# MotorBoard_PowerDistribution.net
KiCad netlist of a schematic drawn in Altium Designer
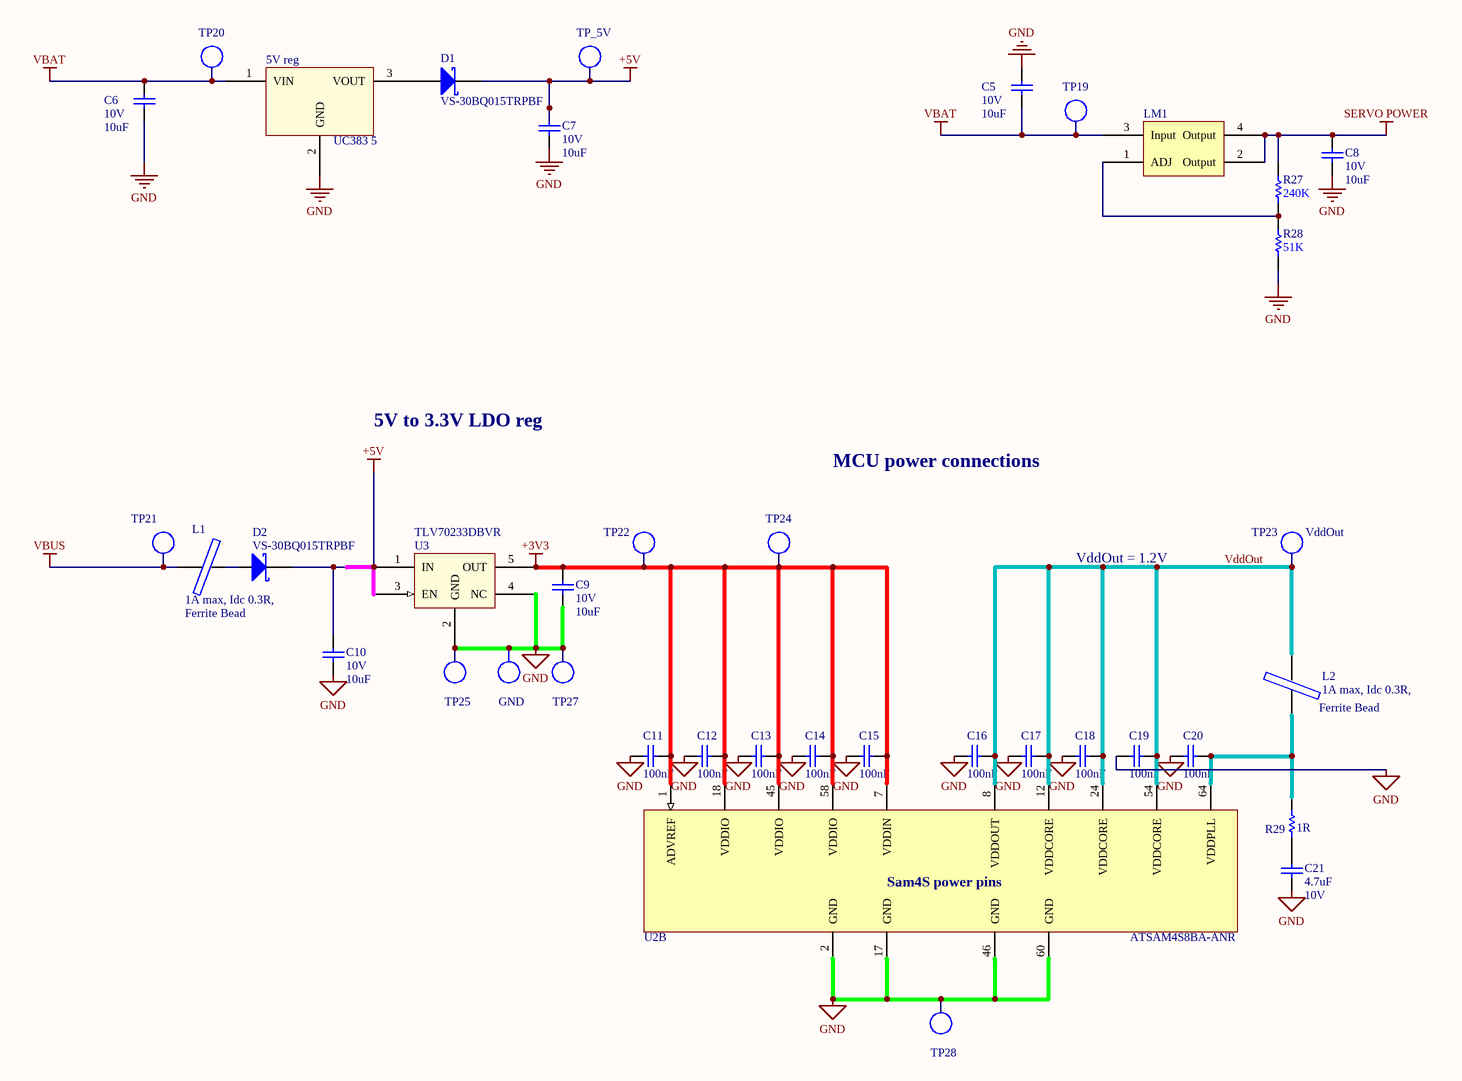
[diagram p0: MotorBoard_PowerDistribution.SchDoc]

(export (version "E")
  (design (tool "Eeschema 10.0.6"))
  (components
    (comp (ref "5V reg")
      (value "UC383 5")
      (footprint "UC383-5")
      (libsource (lib "UC383_5_Throughole_Regulator") (part "UC383 5"))
    )
    (comp (ref "C5")
      (value "10uF")
      (footprint "CAPC1608L")
      (description "CAP CER 10UF X5R +-20% 10V 0603")
      (fields (field (name "VOLTAGE - RATED") "10V"))
      (libsource (lib "ECE Components_15_7") (part "CC_10uF_0603"))
    )
    (comp (ref "C6")
      (value "10uF")
      (footprint "CAPC1608L")
      (description "CAP CER 10UF X5R +-20% 10V 0603")
      (fields (field (name "VOLTAGE - RATED") "10V"))
      (libsource (lib "ECE Components_15_7") (part "CC_10uF_0603"))
    )
    (comp (ref "C7")
      (value "10uF")
      (footprint "CAPC1608L")
      (description "CAP CER 10UF X5R +-20% 10V 0603")
      (fields (field (name "VOLTAGE - RATED") "10V"))
      (libsource (lib "ECE Components_15_7") (part "CC_10uF_0603"))
    )
    (comp (ref "C8")
      (value "10uF")
      (footprint "CAPC1608L")
      (description "CAP CER 10UF X5R +-20% 10V 0603")
      (fields (field (name "VOLTAGE - RATED") "10V"))
      (libsource (lib "ECE Components_15_7") (part "CC_10uF_0603"))
    )
    (comp (ref "C9")
      (value "10uF")
      (footprint "CAPC1608L")
      (description "CAP CER 10UF X5R +-20% 10V 0603")
      (fields (field (name "VOLTAGE - RATED") "10V"))
      (libsource (lib "ECE Components_15_7") (part "CC_10uF_0603"))
    )
    (comp (ref "C10")
      (value "10uF")
      (footprint "CAPC1608L")
      (description "CAP CER 10UF X5R +-20% 10V 0603")
      (fields (field (name "VOLTAGE - RATED") "10V"))
      (libsource (lib "ECE Components_15_7") (part "CC_10uF_0603"))
    )
    (comp (ref "C11")
      (value "100nF")
      (footprint "CAPC1608L")
      (description "CAP CER 100nF X7R +-10% 50V 0603")
      (libsource (lib "ECE Components_15_7") (part "CC_100nF_0603"))
    )
    (comp (ref "C12")
      (value "100nF")
      (footprint "CAPC1608L")
      (description "CAP CER 100nF X7R +-10% 50V 0603")
      (libsource (lib "ECE Components_15_7") (part "CC_100nF_0603"))
    )
    (comp (ref "C13")
      (value "100nF")
      (footprint "CAPC1608L")
      (description "CAP CER 100nF X7R +-10% 50V 0603")
      (libsource (lib "ECE Components_15_7") (part "CC_100nF_0603"))
    )
    (comp (ref "C14")
      (value "100nF")
      (footprint "CAPC1608L")
      (description "CAP CER 100nF X7R +-10% 50V 0603")
      (libsource (lib "ECE Components_15_7") (part "CC_100nF_0603"))
    )
    (comp (ref "C15")
      (value "100nF")
      (footprint "CAPC1608L")
      (description "CAP CER 100nF X7R +-10% 50V 0603")
      (libsource (lib "ECE Components_15_7") (part "CC_100nF_0603"))
    )
    (comp (ref "C16")
      (value "100nF")
      (footprint "CAPC1608L")
      (description "CAP CER 100nF X7R +-10% 50V 0603")
      (libsource (lib "ECE Components_15_7") (part "CC_100nF_0603"))
    )
    (comp (ref "C17")
      (value "100nF")
      (footprint "CAPC1608L")
      (description "CAP CER 100nF X7R +-10% 50V 0603")
      (libsource (lib "ECE Components_15_7") (part "CC_100nF_0603"))
    )
    (comp (ref "C18")
      (value "100nF")
      (footprint "CAPC1608L")
      (description "CAP CER 100nF X7R +-10% 50V 0603")
      (libsource (lib "ECE Components_15_7") (part "CC_100nF_0603"))
    )
    (comp (ref "C19")
      (value "100nF")
      (footprint "CAPC1608L")
      (description "CAP CER 100nF X7R +-10% 50V 0603")
      (libsource (lib "ECE Components_15_7") (part "CC_100nF_0603"))
    )
    (comp (ref "C20")
      (value "100nF")
      (footprint "CAPC1608L")
      (description "CAP CER 100nF X7R +-10% 50V 0603")
      (libsource (lib "ECE Components_15_7") (part "CC_100nF_0603"))
    )
    (comp (ref "C21")
      (value "4.7uF")
      (footprint "CAPC1608N")
      (description "CAP CER 4.7uF X5R +-20%  10V 0603")
      (fields (field (name "MAX VOLTAGE") "10V"))
      (libsource (lib "ECE Components_15_7") (part "CC_4.7uF_0603"))
    )
    (comp (ref "D1")
      (value "VS-30BQ015TRPBF")
      (footprint "SMC")
      (description "DIODE SCHOTTKY 15V 3A SMC")
      (fields
        (field (name "MANUFACTURER") "Vishay Semiconductor Diodes Division")
        (field (name "MANUFACTURER PART NUMBER") "VS-30BQ015TRPBF")
      )
      (libsource (lib "ECE Components_15_8") (part "DS_VS-30BQD015TRPBF"))
    )
    (comp (ref "D2")
      (value "VS-30BQ015TRPBF")
      (footprint "SMC")
      (description "DIODE SCHOTTKY 15V 3A SMC")
      (fields
        (field (name "MANUFACTURER") "Vishay Semiconductor Diodes Division")
        (field (name "MANUFACTURER PART NUMBER") "VS-30BQ015TRPBF")
      )
      (libsource (lib "ECE Components_15_8") (part "DS_VS-30BQD015TRPBF"))
    )
    (comp (ref "GND")
      (value "TP")
      (footprint "TP_1206")
      (description "Test-Point 3.3x1.6x2.1mm SMD")
      (fields
        (field (name "MANUFACTURER") "Harwin Inc")
        (field (name "MANUFACTURER PART NUMBER") "S1751-46R")
      )
      (libsource (lib "ECE Components_15_8") (part "TP_1206"))
    )
    (comp (ref "L1")
      (value "Ferrite Bead")
      (footprint "INDC3216L")
      (description "Ferrite Bead, Rdc 0.3R, Z100MHZ 600R, Imax 1A, SMD 1206")
      (fields
        (field (name "MANUFACTURER") "FAIR-RITE")
        (field (name "MANUFACTURER PART NUMBER") "2512066017Y1")
        (field (name "ALTIUM_VALUE") "1A max, Idc 0.3R,")
      )
      (libsource (lib "ECE Components_15_7") (part "IN_Ferrite-Bead"))
    )
    (comp (ref "L2")
      (value "Ferrite Bead")
      (footprint "INDC3216L")
      (description "Ferrite Bead, Rdc 0.3R, Z100MHZ 600R, Imax 1A, SMD 1206")
      (fields
        (field (name "MANUFACTURER") "FAIR-RITE")
        (field (name "MANUFACTURER PART NUMBER") "2512066017Y1")
        (field (name "ALTIUM_VALUE") "1A max, Idc 0.3R,")
      )
      (libsource (lib "ECE Components_15_7") (part "IN_Ferrite-Bead"))
    )
    (comp (ref "LM1")
      (value "Surface mount regulator, texas instruments")
      (footprint "LM317")
      (libsource (lib "surfacemountreg") (part "LM317 ADJ"))
    )
    (comp (ref "R27")
      (value "240K")
      (footprint "RESC1608L")
      (description "RES 240K OHM 1/10W 5% 0603 SMD")
      (libsource (lib "ECE Components_16_2") (part "RS_240K"))
    )
    (comp (ref "R28")
      (value "51K")
      (footprint "RESC1608L")
      (description "RES 51.0K OHM 1/10W 5% 0603 SMD")
      (libsource (lib "ECE Components_15_8") (part "RS_51K"))
    )
    (comp (ref "R29")
      (value "1R")
      (footprint "RESC3216L")
      (description "RES 1R OHM 1/4W 5% 1206 SMD")
      (libsource (lib "ECE Components_15_7") (part "RT_1R"))
    )
    (comp (ref "TP19")
      (value "USB_N")
      (footprint "TP_0805")
      (description "Test Point 2.0X0.9X1.2mm SMD")
      (fields
        (field (name "MANUFACTURER") "TE Connectivity AMP Connectors")
        (field (name "MANUFACTURER PART NUMBER") "1625854-2")
      )
      (libsource (lib "ECE Components_15_7") (part "TP_0805"))
    )
    (comp (ref "TP20")
      (value "USB_N")
      (footprint "TP_0805")
      (description "Test Point 2.0X0.9X1.2mm SMD")
      (fields
        (field (name "MANUFACTURER") "TE Connectivity AMP Connectors")
        (field (name "MANUFACTURER PART NUMBER") "1625854-2")
      )
      (libsource (lib "ECE Components_15_7") (part "TP_0805"))
    )
    (comp (ref "TP21")
      (value "V_Bus")
      (footprint "TP_0805")
      (description "Test Point 2.0X0.9X1.2mm SMD")
      (fields
        (field (name "MANUFACTURER") "TE Connectivity AMP Connectors")
        (field (name "MANUFACTURER PART NUMBER") "1625854-2")
      )
      (libsource (lib "ECE Components_15_7") (part "TP_0805"))
    )
    (comp (ref "TP22")
      (value "3V3")
      (footprint "TP_0805")
      (description "Test Point 2.0X0.9X1.2mm SMD")
      (fields
        (field (name "MANUFACTURER") "TE Connectivity AMP Connectors")
        (field (name "MANUFACTURER PART NUMBER") "1625854-2")
      )
      (libsource (lib "ECE Components_15_7") (part "TP_0805"))
    )
    (comp (ref "TP23")
      (value "VddOut")
      (footprint "TP_0805")
      (description "Test Point 2.0X0.9X1.2mm SMD")
      (fields
        (field (name "MANUFACTURER") "TE Connectivity AMP Connectors")
        (field (name "MANUFACTURER PART NUMBER") "1625854-2")
      )
      (libsource (lib "ECE Components_15_7") (part "TP_0805"))
    )
    (comp (ref "TP24")
      (value "USB_N")
      (footprint "TP_0805")
      (description "Test Point 2.0X0.9X1.2mm SMD")
      (fields
        (field (name "MANUFACTURER") "TE Connectivity AMP Connectors")
        (field (name "MANUFACTURER PART NUMBER") "1625854-2")
      )
      (libsource (lib "ECE Components_15_7") (part "TP_0805"))
    )
    (comp (ref "TP25")
      (value "Gnd")
      (footprint "TP_0805")
      (description "Test Point 2.0X0.9X1.2mm SMD")
      (fields
        (field (name "MANUFACTURER") "TE Connectivity AMP Connectors")
        (field (name "MANUFACTURER PART NUMBER") "1625854-2")
      )
      (libsource (lib "ECE Components_15_7") (part "TP_0805"))
    )
    (comp (ref "TP27")
      (value "USB_N")
      (footprint "TP_0805")
      (description "Test Point 2.0X0.9X1.2mm SMD")
      (fields
        (field (name "MANUFACTURER") "TE Connectivity AMP Connectors")
        (field (name "MANUFACTURER PART NUMBER") "1625854-2")
      )
      (libsource (lib "ECE Components_15_7") (part "TP_0805"))
    )
    (comp (ref "TP28")
      (value "Gnd")
      (footprint "TP_0805")
      (description "Test Point 2.0X0.9X1.2mm SMD")
      (fields
        (field (name "MANUFACTURER") "TE Connectivity AMP Connectors")
        (field (name "MANUFACTURER PART NUMBER") "1625854-2")
      )
      (libsource (lib "ECE Components_15_7") (part "TP_0805"))
    )
    (comp (ref "TP_5V")
      (value "USB_N")
      (footprint "TP_0805")
      (description "Test Point 2.0X0.9X1.2mm SMD")
      (fields
        (field (name "MANUFACTURER") "TE Connectivity AMP Connectors")
        (field (name "MANUFACTURER PART NUMBER") "1625854-2")
      )
      (libsource (lib "ECE Components_15_7") (part "TP_0805"))
    )
    (comp (ref "U2")
      (value "ATSAM4S8BA-ANR")
      (footprint "LQFP64_L")
      (description "IC MCU 32BIT 512KB FLASH 64LQFP")
      (fields (field (name "MANUFACTURER") "Atmel"))
      (libsource (lib "ECE Components_15_7") (part "SE_ATSAM4S16BA-MU"))
    )
    (comp (ref "U3")
      (value "TLV70233DBVR")
      (footprint "SOT95P280X145-5N")
      (description "IC REG LDO 3.3V 0.3A SOT23-5")
      (fields
        (field (name "MANUFACTURER") "Texas Instruments")
        (field (name "MANUFACTURER PART NUMBER") "TLV70233DBVR")
      )
      (libsource (lib "ECE Components_15_7") (part "SV_TLV70233DBVR"))
    )
  )
  (nets
    (net (code "1") (name "+3V3") (class "Default")
      (node (ref "C11") (pin "2") (pinfunction "2_2") (pintype "passive"))
      (node (ref "C12") (pin "2") (pinfunction "2_2") (pintype "passive"))
      (node (ref "C13") (pin "2") (pinfunction "2_2") (pintype "passive"))
      (node (ref "C14") (pin "2") (pinfunction "2_2") (pintype "passive"))
      (node (ref "C15") (pin "2") (pinfunction "2_2") (pintype "passive"))
      (node (ref "C9") (pin "1") (pinfunction "1_1") (pintype "passive"))
      (node (ref "TP22") (pin "1") (pinfunction "TP_1") (pintype "passive"))
      (node (ref "TP24") (pin "1") (pinfunction "TP_1") (pintype "passive"))
      (node (ref "U2") (pin "1") (pinfunction "ADVREF_1") (pintype "input"))
      (node (ref "U2") (pin "18") (pinfunction "VDDIO_18") (pintype "power_in"))
      (node (ref "U2") (pin "45") (pinfunction "VDDIO_45") (pintype "power_in"))
      (node (ref "U2") (pin "58") (pinfunction "VDDIO_58") (pintype "power_in"))
      (node (ref "U2") (pin "7") (pinfunction "VDDIN_7") (pintype "power_in"))
      (node (ref "U3") (pin "5") (pinfunction "OUT_5") (pintype "power_in"))
    )
    (net (code "2") (name "+5V") (class "Default")
      (node (ref "C10") (pin "1") (pinfunction "1_1") (pintype "passive"))
      (node (ref "C7") (pin "1") (pinfunction "1_1") (pintype "passive"))
      (node (ref "D1") (pin "2") (pinfunction "K_2") (pintype "passive"))
      (node (ref "D2") (pin "2") (pinfunction "K_2") (pintype "passive"))
      (node (ref "TP_5V") (pin "1") (pinfunction "TP_1") (pintype "passive"))
      (node (ref "U3") (pin "1") (pinfunction "IN_1") (pintype "power_in"))
      (node (ref "U3") (pin "3") (pinfunction "EN_3") (pintype "input"))
    )
    (net (code "3") (name "/VddOut") (class "Default")
      (node (ref "C16") (pin "2") (pinfunction "2_2") (pintype "passive"))
      (node (ref "C17") (pin "2") (pinfunction "2_2") (pintype "passive"))
      (node (ref "C18") (pin "2") (pinfunction "2_2") (pintype "passive"))
      (node (ref "C19") (pin "2") (pinfunction "2_2") (pintype "passive"))
      (node (ref "L2") (pin "2") (pinfunction "2_2") (pintype "passive"))
      (node (ref "TP23") (pin "1") (pinfunction "TP_1") (pintype "passive"))
      (node (ref "U2") (pin "12") (pinfunction "VDDCORE_12") (pintype "power_in"))
      (node (ref "U2") (pin "24") (pinfunction "VDDCORE_24") (pintype "power_in"))
      (node (ref "U2") (pin "54") (pinfunction "VDDCORE_54") (pintype "power_in"))
      (node (ref "U2") (pin "8") (pinfunction "VDDOUT_8") (pintype "power_in"))
    )
    (net (code "4") (name "GND") (class "Default")
      (node (ref "5V reg") (pin "2") (pinfunction "GND_2") (pintype "passive"))
      (node (ref "C10") (pin "2") (pinfunction "2_2") (pintype "passive"))
      (node (ref "C11") (pin "1") (pinfunction "1_1") (pintype "passive"))
      (node (ref "C12") (pin "1") (pinfunction "1_1") (pintype "passive"))
      (node (ref "C13") (pin "1") (pinfunction "1_1") (pintype "passive"))
      (node (ref "C14") (pin "1") (pinfunction "1_1") (pintype "passive"))
      (node (ref "C15") (pin "1") (pinfunction "1_1") (pintype "passive"))
      (node (ref "C16") (pin "1") (pinfunction "1_1") (pintype "passive"))
      (node (ref "C17") (pin "1") (pinfunction "1_1") (pintype "passive"))
      (node (ref "C18") (pin "1") (pinfunction "1_1") (pintype "passive"))
      (node (ref "C19") (pin "1") (pinfunction "1_1") (pintype "passive"))
      (node (ref "C20") (pin "1") (pinfunction "1_1") (pintype "passive"))
      (node (ref "C21") (pin "1") (pinfunction "1_1") (pintype "passive"))
      (node (ref "C5") (pin "1") (pinfunction "1_1") (pintype "passive"))
      (node (ref "C6") (pin "2") (pinfunction "2_2") (pintype "passive"))
      (node (ref "C7") (pin "2") (pinfunction "2_2") (pintype "passive"))
      (node (ref "C8") (pin "2") (pinfunction "2_2") (pintype "passive"))
      (node (ref "C9") (pin "2") (pinfunction "2_2") (pintype "passive"))
      (node (ref "GND") (pin "1") (pinfunction "1_1") (pintype "passive"))
      (node (ref "R28") (pin "1") (pinfunction "1_1") (pintype "passive"))
      (node (ref "TP25") (pin "1") (pinfunction "TP_1") (pintype "passive"))
      (node (ref "TP27") (pin "1") (pinfunction "TP_1") (pintype "passive"))
      (node (ref "TP28") (pin "1") (pinfunction "TP_1") (pintype "passive"))
      (node (ref "U2") (pin "17") (pinfunction "GND_17") (pintype "power_in"))
      (node (ref "U2") (pin "2") (pinfunction "GND_2") (pintype "power_in"))
      (node (ref "U2") (pin "46") (pinfunction "GND_46") (pintype "power_in"))
      (node (ref "U2") (pin "60") (pinfunction "GND_60") (pintype "power_in"))
      (node (ref "U3") (pin "2") (pinfunction "GND_2") (pintype "power_in"))
      (node (ref "U3") (pin "4") (pinfunction "NC_4") (pintype "passive"))
    )
    (net (code "5") (name "Net-(5V reg-VOUT)") (class "Default")
      (node (ref "5V reg") (pin "3") (pinfunction "VOUT_3") (pintype "passive"))
      (node (ref "D1") (pin "1") (pinfunction "A_1") (pintype "passive"))
    )
    (net (code "6") (name "Net-(C21-Pad2)") (class "Default")
      (node (ref "C21") (pin "2") (pinfunction "2_2") (pintype "passive"))
      (node (ref "R29") (pin "1") (pinfunction "1_1") (pintype "passive"))
    )
    (net (code "7") (name "Net-(D2-A)") (class "Default")
      (node (ref "D2") (pin "1") (pinfunction "A_1") (pintype "passive"))
      (node (ref "L1") (pin "2") (pinfunction "2_2") (pintype "passive"))
    )
    (net (code "8") (name "Net-(LM1-ADJ)") (class "Default")
      (node (ref "LM1") (pin "1") (pinfunction "ADJ_1") (pintype "power_in"))
      (node (ref "R27") (pin "1") (pinfunction "1_1") (pintype "passive"))
      (node (ref "R28") (pin "2") (pinfunction "2_2") (pintype "passive"))
    )
    (net (code "9") (name "Net-(U2B-VDDPLL)") (class "Default")
      (node (ref "C20") (pin "2") (pinfunction "2_2") (pintype "passive"))
      (node (ref "L2") (pin "1") (pinfunction "1_1") (pintype "passive"))
      (node (ref "R29") (pin "2") (pinfunction "2_2") (pintype "passive"))
      (node (ref "U2") (pin "64") (pinfunction "VDDPLL_64") (pintype "power_in"))
    )
    (net (code "10") (name "SERVO POWER") (class "Default")
      (node (ref "C8") (pin "1") (pinfunction "1_1") (pintype "passive"))
      (node (ref "LM1") (pin "2") (pinfunction "Output_2") (pintype "power_in"))
      (node (ref "LM1") (pin "4") (pinfunction "Output_4") (pintype "power_in"))
      (node (ref "R27") (pin "2") (pinfunction "2_2") (pintype "passive"))
    )
    (net (code "11") (name "VBAT") (class "Default")
      (node (ref "5V reg") (pin "1") (pinfunction "VIN_1") (pintype "passive"))
      (node (ref "C5") (pin "2") (pinfunction "2_2") (pintype "passive"))
      (node (ref "C6") (pin "1") (pinfunction "1_1") (pintype "passive"))
      (node (ref "LM1") (pin "3") (pinfunction "Input_3") (pintype "power_in"))
      (node (ref "TP19") (pin "1") (pinfunction "TP_1") (pintype "passive"))
      (node (ref "TP20") (pin "1") (pinfunction "TP_1") (pintype "passive"))
    )
    (net (code "12") (name "VBUS") (class "Default")
      (node (ref "L1") (pin "1") (pinfunction "1_1") (pintype "passive"))
      (node (ref "TP21") (pin "1") (pinfunction "TP_1") (pintype "passive"))
    )
  )
)
